# TDC.net
KiCad netlist of a schematic drawn in Altium Designer
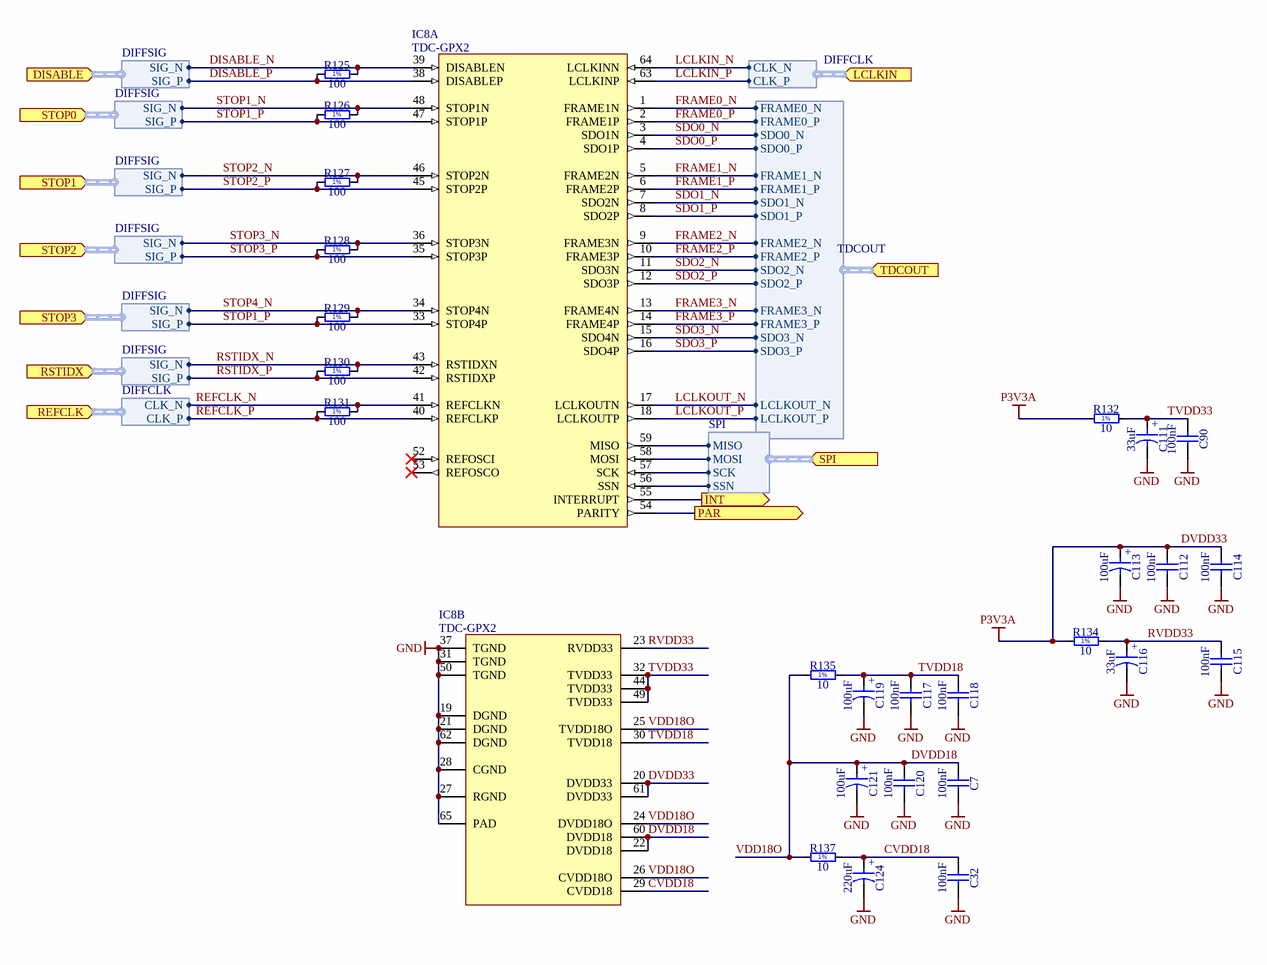
[diagram p0: TDC.SchDoc]

(export (version "E")
  (design (tool "Eeschema 10.0.6"))
  (components
    (comp (ref "C7")
      (value "100nF")
      (footprint "CAPC0603X33N")
      (description "Non-polarised capacitor")
      (fields
        (field (name "PART NUMBER") "CC0201_100NF_6.3V_10%_X5R")
        (field (name "VOLTAGE") "6.3V")
        (field (name "AUTHOR") "CERN DEM JLC")
      )
      (libsource (lib "Capacitors") (part "Capacitor - non polarized"))
    )
    (comp (ref "C32")
      (value "100nF")
      (footprint "CAPC0603X33N")
      (description "Non-polarised capacitor")
      (fields
        (field (name "PART NUMBER") "CC0201_100NF_6.3V_10%_X5R")
        (field (name "VOLTAGE") "6.3V")
        (field (name "AUTHOR") "CERN DEM JLC")
      )
      (libsource (lib "Capacitors") (part "Capacitor - non polarized"))
    )
    (comp (ref "C90")
      (value "100nF")
      (footprint "CAPC0603X33N")
      (description "Non-polarised capacitor")
      (fields
        (field (name "PART NUMBER") "CC0201_100NF_6.3V_10%_X5R")
        (field (name "VOLTAGE") "6.3V")
        (field (name "AUTHOR") "CERN DEM JLC")
      )
      (libsource (lib "Capacitors") (part "Capacitor - non polarized"))
    )
    (comp (ref "C111")
      (value "33uF")
      (footprint "CAPMP3216X180N")
      (description "Polarised capacitor")
      (fields
        (field (name "PART NUMBER") "CTE3216-18_33UF_4V_10%")
        (field (name "VOLTAGE") "4V")
        (field (name "AUTHOR") "CERN DEM JLC")
      )
      (libsource (lib "Capacitors") (part "Capacitor - polarized"))
    )
    (comp (ref "C112")
      (value "100nF")
      (footprint "CAPC0603X33N")
      (description "Non-polarised capacitor")
      (fields
        (field (name "PART NUMBER") "CC0201_100NF_6.3V_10%_X5R")
        (field (name "VOLTAGE") "6.3V")
        (field (name "AUTHOR") "CERN DEM JLC")
      )
      (libsource (lib "Capacitors") (part "Capacitor - non polarized"))
    )
    (comp (ref "C113")
      (value "100uF")
      (footprint "CAPMP3216X180N")
      (description "Polarised capacitor")
      (fields
        (field (name "PART NUMBER") "CTE3216-18_100UF_6.3V_20%_ESR0500_AVX_TLJ")
        (field (name "VOLTAGE") "6.3V")
        (field (name "AUTHOR") "CERN DEM JLC")
      )
      (libsource (lib "Capacitors") (part "Capacitor - polarized"))
    )
    (comp (ref "C114")
      (value "100nF")
      (footprint "CAPC0603X33N")
      (description "Non-polarised capacitor")
      (fields
        (field (name "PART NUMBER") "CC0201_100NF_6.3V_10%_X5R")
        (field (name "VOLTAGE") "6.3V")
        (field (name "AUTHOR") "CERN DEM JLC")
      )
      (libsource (lib "Capacitors") (part "Capacitor - non polarized"))
    )
    (comp (ref "C115")
      (value "100nF")
      (footprint "CAPC0603X33N")
      (description "Non-polarised capacitor")
      (fields
        (field (name "PART NUMBER") "CC0201_100NF_6.3V_10%_X5R")
        (field (name "VOLTAGE") "6.3V")
        (field (name "AUTHOR") "CERN DEM JLC")
      )
      (libsource (lib "Capacitors") (part "Capacitor - non polarized"))
    )
    (comp (ref "C116")
      (value "33uF")
      (footprint "CAPMP3216X180N")
      (description "Polarised capacitor")
      (fields
        (field (name "PART NUMBER") "CTE3216-18_33UF_4V_10%")
        (field (name "VOLTAGE") "4V")
        (field (name "AUTHOR") "CERN DEM JLC")
      )
      (libsource (lib "Capacitors") (part "Capacitor - polarized"))
    )
    (comp (ref "C117")
      (value "100nF")
      (footprint "CAPC0603X33N")
      (description "Non-polarised capacitor")
      (fields
        (field (name "PART NUMBER") "CC0201_100NF_6.3V_10%_X5R")
        (field (name "VOLTAGE") "6.3V")
        (field (name "AUTHOR") "CERN DEM JLC")
      )
      (libsource (lib "Capacitors") (part "Capacitor - non polarized"))
    )
    (comp (ref "C118")
      (value "100nF")
      (footprint "CAPC0603X33N")
      (description "Non-polarised capacitor")
      (fields
        (field (name "PART NUMBER") "CC0201_100NF_6.3V_10%_X5R")
        (field (name "VOLTAGE") "6.3V")
        (field (name "AUTHOR") "CERN DEM JLC")
      )
      (libsource (lib "Capacitors") (part "Capacitor - non polarized"))
    )
    (comp (ref "C119")
      (value "100uF")
      (footprint "CAPMP3216X180N")
      (description "Polarised capacitor")
      (fields
        (field (name "PART NUMBER") "CTE3216-18_100UF_6.3V_20%_ESR0500_AVX_TLJ")
        (field (name "VOLTAGE") "6.3V")
        (field (name "AUTHOR") "CERN DEM JLC")
      )
      (libsource (lib "Capacitors") (part "Capacitor - polarized"))
    )
    (comp (ref "C120")
      (value "100nF")
      (footprint "CAPC0603X33N")
      (description "Non-polarised capacitor")
      (fields
        (field (name "PART NUMBER") "CC0201_100NF_6.3V_10%_X5R")
        (field (name "VOLTAGE") "6.3V")
        (field (name "AUTHOR") "CERN DEM JLC")
      )
      (libsource (lib "Capacitors") (part "Capacitor - non polarized"))
    )
    (comp (ref "C121")
      (value "100uF")
      (footprint "CAPMP3216X180N")
      (description "Polarised capacitor")
      (fields
        (field (name "PART NUMBER") "CTE3216-18_100UF_6.3V_20%_ESR0500_AVX_TLJ")
        (field (name "VOLTAGE") "6.3V")
        (field (name "AUTHOR") "CERN DEM JLC")
      )
      (libsource (lib "Capacitors") (part "Capacitor - polarized"))
    )
    (comp (ref "C124")
      (value "220uF")
      (footprint "CAPMP3528X210N")
      (description "Polarised capacitor")
      (fields
        (field (name "PART NUMBER") "CTE3528-21_220UF_2.5V_10%")
        (field (name "VOLTAGE") "2.5V")
        (field (name "AUTHOR") "CERN DEM JLC")
      )
      (libsource (lib "Capacitors") (part "Capacitor - polarized"))
    )
    (comp (ref "IC8")
      (value "TDC-GPX2")
      (footprint "QFN50P900X900X100-65N-S615")
      (description "4-Channel Time-to-Digital Converter")
      (fields (field (name "MANUFACTURER") "ACAM MESS-ELECTRONIC") (field (name "AUTHOR") "GK"))
      (libsource (lib "LIBRARY_SCH") (part "TDC-GPX2"))
    )
    (comp (ref "R125")
      (value "100")
      (footprint "RESC0603X28N")
      (description "Resistor - 1%")
      (fields
        (field (name "PART NUMBER") "R0201_100R_1%_0.05W_200PPM")
        (field (name "POWER") "0.05W")
        (field (name "AUTHOR") "CERN DEM JLC")
      )
      (libsource (lib "Resistors") (part "Resistor - 1%"))
    )
    (comp (ref "R126")
      (value "100")
      (footprint "RESC0603X28N")
      (description "Resistor - 1%")
      (fields
        (field (name "PART NUMBER") "R0201_100R_1%_0.05W_200PPM")
        (field (name "POWER") "0.05W")
        (field (name "AUTHOR") "CERN DEM JLC")
      )
      (libsource (lib "Resistors") (part "Resistor - 1%"))
    )
    (comp (ref "R127")
      (value "100")
      (footprint "RESC0603X28N")
      (description "Resistor - 1%")
      (fields
        (field (name "PART NUMBER") "R0201_100R_1%_0.05W_200PPM")
        (field (name "POWER") "0.05W")
        (field (name "AUTHOR") "CERN DEM JLC")
      )
      (libsource (lib "Resistors") (part "Resistor - 1%"))
    )
    (comp (ref "R128")
      (value "100")
      (footprint "RESC0603X28N")
      (description "Resistor - 1%")
      (fields
        (field (name "PART NUMBER") "R0201_100R_1%_0.05W_200PPM")
        (field (name "POWER") "0.05W")
        (field (name "AUTHOR") "CERN DEM JLC")
      )
      (libsource (lib "Resistors") (part "Resistor - 1%"))
    )
    (comp (ref "R129")
      (value "100")
      (footprint "RESC0603X28N")
      (description "Resistor - 1%")
      (fields
        (field (name "PART NUMBER") "R0201_100R_1%_0.05W_200PPM")
        (field (name "POWER") "0.05W")
        (field (name "AUTHOR") "CERN DEM JLC")
      )
      (libsource (lib "Resistors") (part "Resistor - 1%"))
    )
    (comp (ref "R130")
      (value "100")
      (footprint "RESC0603X28N")
      (description "Resistor - 1%")
      (fields
        (field (name "PART NUMBER") "R0201_100R_1%_0.05W_200PPM")
        (field (name "POWER") "0.05W")
        (field (name "AUTHOR") "CERN DEM JLC")
      )
      (libsource (lib "Resistors") (part "Resistor - 1%"))
    )
    (comp (ref "R131")
      (value "100")
      (footprint "RESC0603X28N")
      (description "Resistor - 1%")
      (fields
        (field (name "PART NUMBER") "R0201_100R_1%_0.05W_200PPM")
        (field (name "POWER") "0.05W")
        (field (name "AUTHOR") "CERN DEM JLC")
      )
      (libsource (lib "Resistors") (part "Resistor - 1%"))
    )
    (comp (ref "R132")
      (value "10")
      (footprint "RESC1005X40N")
      (description "Resistor - 1%")
      (fields
        (field (name "PART NUMBER") "R0402_10R_1%_0.0625W_200PPM")
        (field (name "POWER") "0.0625W")
        (field (name "AUTHOR") "CERN DEM JLC")
      )
      (libsource (lib "Resistors") (part "Resistor - 1%"))
    )
    (comp (ref "R134")
      (value "10")
      (footprint "RESC1005X40N")
      (description "Resistor - 1%")
      (fields
        (field (name "PART NUMBER") "R0402_10R_1%_0.0625W_200PPM")
        (field (name "POWER") "0.0625W")
        (field (name "AUTHOR") "CERN DEM JLC")
      )
      (libsource (lib "Resistors") (part "Resistor - 1%"))
    )
    (comp (ref "R135")
      (value "10")
      (footprint "RESC1005X40N")
      (description "Resistor - 1%")
      (fields
        (field (name "PART NUMBER") "R0402_10R_1%_0.0625W_200PPM")
        (field (name "POWER") "0.0625W")
        (field (name "AUTHOR") "CERN DEM JLC")
      )
      (libsource (lib "Resistors") (part "Resistor - 1%"))
    )
    (comp (ref "R137")
      (value "10")
      (footprint "RESC1005X40N")
      (description "Resistor - 1%")
      (fields
        (field (name "PART NUMBER") "R0402_10R_1%_0.0625W_200PPM")
        (field (name "POWER") "0.0625W")
        (field (name "AUTHOR") "CERN DEM JLC")
      )
      (libsource (lib "Resistors") (part "Resistor - 1%"))
    )
  )
  (nets
    (net (code "5") (name "/CVDD18") (class "Default")
      (node (ref "C124") (pin "1") (pinfunction "1_1") (pintype "passive"))
      (node (ref "C32") (pin "1") (pinfunction "1_1") (pintype "passive"))
      (node (ref "IC8") (pin "29") (pinfunction "CVDD18_29") (pintype "power_in"))
      (node (ref "R137") (pin "2") (pinfunction "2_2") (pintype "passive"))
    )
    (net (code "6") (name "/DISABLE_N") (class "Default")
      (node (ref "IC8") (pin "39") (pinfunction "DISABLEN_39") (pintype "input"))
      (node (ref "R125") (pin "2") (pinfunction "2_2") (pintype "passive"))
    )
    (net (code "7") (name "/DISABLE_P") (class "Default")
      (node (ref "IC8") (pin "38") (pinfunction "DISABLEP_38") (pintype "input"))
      (node (ref "R125") (pin "1") (pinfunction "1_1") (pintype "passive"))
    )
    (net (code "8") (name "/DVDD18") (class "Default")
      (node (ref "C120") (pin "1") (pinfunction "1_1") (pintype "passive"))
      (node (ref "C121") (pin "1") (pinfunction "1_1") (pintype "passive"))
      (node (ref "C7") (pin "1") (pinfunction "1_1") (pintype "passive"))
      (node (ref "IC8") (pin "22") (pinfunction "DVDD18_22") (pintype "power_in"))
      (node (ref "IC8") (pin "24") (pinfunction "DVDD18O_24") (pintype "power_in"))
      (node (ref "IC8") (pin "25") (pinfunction "TVDD18O_25") (pintype "power_in"))
      (node (ref "IC8") (pin "26") (pinfunction "CVDD18O_26") (pintype "power_in"))
      (node (ref "IC8") (pin "60") (pinfunction "DVDD18_60") (pintype "power_in"))
      (node (ref "R135") (pin "1") (pinfunction "1_1") (pintype "passive"))
      (node (ref "R137") (pin "1") (pinfunction "1_1") (pintype "passive"))
    )
    (net (code "9") (name "/FRAME0_N") (class "Default")
      (node (ref "IC8") (pin "1") (pinfunction "FRAME1N_1") (pintype "output"))
    )
    (net (code "10") (name "/FRAME0_P") (class "Default")
      (node (ref "IC8") (pin "2") (pinfunction "FRAME1P_2") (pintype "output"))
    )
    (net (code "11") (name "/FRAME1_N") (class "Default")
      (node (ref "IC8") (pin "5") (pinfunction "FRAME2N_5") (pintype "output"))
    )
    (net (code "12") (name "/FRAME1_P") (class "Default")
      (node (ref "IC8") (pin "6") (pinfunction "FRAME2P_6") (pintype "output"))
    )
    (net (code "13") (name "/FRAME2_N") (class "Default")
      (node (ref "IC8") (pin "9") (pinfunction "FRAME3N_9") (pintype "output"))
    )
    (net (code "14") (name "/FRAME2_P") (class "Default")
      (node (ref "IC8") (pin "10") (pinfunction "FRAME3P_10") (pintype "output"))
    )
    (net (code "15") (name "/FRAME3_N") (class "Default")
      (node (ref "IC8") (pin "13") (pinfunction "FRAME4N_13") (pintype "output"))
    )
    (net (code "16") (name "/FRAME3_P") (class "Default")
      (node (ref "IC8") (pin "14") (pinfunction "FRAME4P_14") (pintype "output"))
    )
    (net (code "17") (name "/INT") (class "Default")
      (node (ref "IC8") (pin "55") (pinfunction "INTERRUPT_55") (pintype "output"))
    )
    (net (code "18") (name "/LCLKIN_N") (class "Default")
      (node (ref "IC8") (pin "64") (pinfunction "LCLKINN_64") (pintype "input"))
    )
    (net (code "19") (name "/LCLKIN_P") (class "Default")
      (node (ref "IC8") (pin "63") (pinfunction "LCLKINP_63") (pintype "input"))
    )
    (net (code "20") (name "/LCLKOUT_N") (class "Default")
      (node (ref "IC8") (pin "17") (pinfunction "LCLKOUTN_17") (pintype "output"))
    )
    (net (code "21") (name "/LCLKOUT_P") (class "Default")
      (node (ref "IC8") (pin "18") (pinfunction "LCLKOUTP_18") (pintype "output"))
    )
    (net (code "22") (name "/MISO") (class "Default")
      (node (ref "IC8") (pin "59") (pinfunction "MISO_59") (pintype "output"))
    )
    (net (code "23") (name "/MOSI") (class "Default")
      (node (ref "IC8") (pin "58") (pinfunction "MOSI_58") (pintype "input"))
    )
    (net (code "24") (name "/PAR") (class "Default")
      (node (ref "IC8") (pin "54") (pinfunction "PARITY_54") (pintype "output"))
    )
    (net (code "25") (name "/REFCLK_N") (class "Default")
      (node (ref "IC8") (pin "41") (pinfunction "REFCLKN_41") (pintype "input"))
      (node (ref "R131") (pin "2") (pinfunction "2_2") (pintype "passive"))
    )
    (net (code "26") (name "/REFCLK_P") (class "Default")
      (node (ref "IC8") (pin "40") (pinfunction "REFCLKP_40") (pintype "input"))
      (node (ref "R131") (pin "1") (pinfunction "1_1") (pintype "passive"))
    )
    (net (code "27") (name "/RSTIDX_N") (class "Default")
      (node (ref "IC8") (pin "43") (pinfunction "RSTIDXN_43") (pintype "input"))
      (node (ref "R130") (pin "2") (pinfunction "2_2") (pintype "passive"))
    )
    (net (code "28") (name "/RSTIDX_P") (class "Default")
      (node (ref "IC8") (pin "42") (pinfunction "RSTIDXP_42") (pintype "input"))
      (node (ref "R130") (pin "1") (pinfunction "1_1") (pintype "passive"))
    )
    (net (code "29") (name "/RVDD33") (class "Default")
      (node (ref "C115") (pin "1") (pinfunction "1_1") (pintype "passive"))
      (node (ref "C116") (pin "1") (pinfunction "1_1") (pintype "passive"))
      (node (ref "IC8") (pin "23") (pinfunction "RVDD33_23") (pintype "power_in"))
      (node (ref "R134") (pin "2") (pinfunction "2_2") (pintype "passive"))
    )
    (net (code "30") (name "/SCK") (class "Default")
      (node (ref "IC8") (pin "57") (pinfunction "SCK_57") (pintype "input"))
    )
    (net (code "31") (name "/SDO0_N") (class "Default")
      (node (ref "IC8") (pin "3") (pinfunction "SDO1N_3") (pintype "output"))
    )
    (net (code "32") (name "/SDO0_P") (class "Default")
      (node (ref "IC8") (pin "4") (pinfunction "SDO1P_4") (pintype "output"))
    )
    (net (code "33") (name "/SDO1_N") (class "Default")
      (node (ref "IC8") (pin "7") (pinfunction "SDO2N_7") (pintype "output"))
    )
    (net (code "34") (name "/SDO1_P") (class "Default")
      (node (ref "IC8") (pin "8") (pinfunction "SDO2P_8") (pintype "output"))
    )
    (net (code "35") (name "/SDO2_N") (class "Default")
      (node (ref "IC8") (pin "11") (pinfunction "SDO3N_11") (pintype "output"))
    )
    (net (code "36") (name "/SDO2_P") (class "Default")
      (node (ref "IC8") (pin "12") (pinfunction "SDO3P_12") (pintype "output"))
    )
    (net (code "37") (name "/SDO3_N") (class "Default")
      (node (ref "IC8") (pin "15") (pinfunction "SDO4N_15") (pintype "output"))
    )
    (net (code "38") (name "/SDO3_P") (class "Default")
      (node (ref "IC8") (pin "16") (pinfunction "SDO4P_16") (pintype "output"))
    )
    (net (code "39") (name "/SSN") (class "Default")
      (node (ref "IC8") (pin "56") (pinfunction "SSN_56") (pintype "input"))
    )
    (net (code "40") (name "/STOP1_N") (class "Default")
      (node (ref "IC8") (pin "48") (pinfunction "STOP1N_48") (pintype "input"))
      (node (ref "R126") (pin "2") (pinfunction "2_2") (pintype "passive"))
    )
    (net (code "41") (name "/STOP1_P") (class "Default")
      (node (ref "IC8") (pin "33") (pinfunction "STOP4P_33") (pintype "input"))
      (node (ref "IC8") (pin "47") (pinfunction "STOP1P_47") (pintype "input"))
      (node (ref "R126") (pin "1") (pinfunction "1_1") (pintype "passive"))
      (node (ref "R129") (pin "1") (pinfunction "1_1") (pintype "passive"))
    )
    (net (code "42") (name "/STOP2_N") (class "Default")
      (node (ref "IC8") (pin "46") (pinfunction "STOP2N_46") (pintype "input"))
      (node (ref "R127") (pin "2") (pinfunction "2_2") (pintype "passive"))
    )
    (net (code "43") (name "/STOP2_P") (class "Default")
      (node (ref "IC8") (pin "45") (pinfunction "STOP2P_45") (pintype "input"))
      (node (ref "R127") (pin "1") (pinfunction "1_1") (pintype "passive"))
    )
    (net (code "44") (name "/STOP3_N") (class "Default")
      (node (ref "IC8") (pin "36") (pinfunction "STOP3N_36") (pintype "input"))
      (node (ref "R128") (pin "2") (pinfunction "2_2") (pintype "passive"))
    )
    (net (code "45") (name "/STOP3_P") (class "Default")
      (node (ref "IC8") (pin "35") (pinfunction "STOP3P_35") (pintype "input"))
      (node (ref "R128") (pin "1") (pinfunction "1_1") (pintype "passive"))
    )
    (net (code "46") (name "/STOP4_N") (class "Default")
      (node (ref "IC8") (pin "34") (pinfunction "STOP4N_34") (pintype "input"))
      (node (ref "R129") (pin "2") (pinfunction "2_2") (pintype "passive"))
    )
    (net (code "47") (name "/TVDD18") (class "Default")
      (node (ref "C117") (pin "1") (pinfunction "1_1") (pintype "passive"))
      (node (ref "C118") (pin "1") (pinfunction "1_1") (pintype "passive"))
      (node (ref "C119") (pin "1") (pinfunction "1_1") (pintype "passive"))
      (node (ref "IC8") (pin "30") (pinfunction "TVDD18_30") (pintype "power_in"))
      (node (ref "R135") (pin "2") (pinfunction "2_2") (pintype "passive"))
    )
    (net (code "48") (name "/TVDD33") (class "Default")
      (node (ref "C111") (pin "1") (pinfunction "1_1") (pintype "passive"))
      (node (ref "C90") (pin "1") (pinfunction "1_1") (pintype "passive"))
      (node (ref "IC8") (pin "32") (pinfunction "TVDD33_32") (pintype "power_in"))
      (node (ref "IC8") (pin "44") (pinfunction "TVDD33_44") (pintype "power_in"))
      (node (ref "IC8") (pin "49") (pinfunction "TVDD33_49") (pintype "power_in"))
      (node (ref "R132") (pin "2") (pinfunction "2_2") (pintype "passive"))
    )
    (net (code "53") (name "GND") (class "Default")
      (node (ref "C111") (pin "2") (pinfunction "2_2") (pintype "passive"))
      (node (ref "C112") (pin "2") (pinfunction "2_2") (pintype "passive"))
      (node (ref "C113") (pin "2") (pinfunction "2_2") (pintype "passive"))
      (node (ref "C114") (pin "2") (pinfunction "2_2") (pintype "passive"))
      (node (ref "C115") (pin "2") (pinfunction "2_2") (pintype "passive"))
      (node (ref "C116") (pin "2") (pinfunction "2_2") (pintype "passive"))
      (node (ref "C117") (pin "2") (pinfunction "2_2") (pintype "passive"))
      (node (ref "C118") (pin "2") (pinfunction "2_2") (pintype "passive"))
      (node (ref "C119") (pin "2") (pinfunction "2_2") (pintype "passive"))
      (node (ref "C120") (pin "2") (pinfunction "2_2") (pintype "passive"))
      (node (ref "C121") (pin "2") (pinfunction "2_2") (pintype "passive"))
      (node (ref "C124") (pin "2") (pinfunction "2_2") (pintype "passive"))
      (node (ref "C32") (pin "2") (pinfunction "2_2") (pintype "passive"))
      (node (ref "C7") (pin "2") (pinfunction "2_2") (pintype "passive"))
      (node (ref "C90") (pin "2") (pinfunction "2_2") (pintype "passive"))
      (node (ref "IC8") (pin "19") (pinfunction "DGND_19") (pintype "power_in"))
      (node (ref "IC8") (pin "21") (pinfunction "DGND_21") (pintype "power_in"))
      (node (ref "IC8") (pin "27") (pinfunction "RGND_27") (pintype "power_in"))
      (node (ref "IC8") (pin "28") (pinfunction "CGND_28") (pintype "power_in"))
      (node (ref "IC8") (pin "31") (pinfunction "TGND_31") (pintype "power_in"))
      (node (ref "IC8") (pin "37") (pinfunction "TGND_37") (pintype "power_in"))
      (node (ref "IC8") (pin "50") (pinfunction "TGND_50") (pintype "power_in"))
      (node (ref "IC8") (pin "62") (pinfunction "DGND_62") (pintype "power_in"))
      (node (ref "IC8") (pin "65") (pinfunction "PAD_65") (pintype "power_in"))
    )
    (net (code "54") (name "P3V3A") (class "Default")
      (node (ref "C112") (pin "1") (pinfunction "1_1") (pintype "passive"))
      (node (ref "C113") (pin "1") (pinfunction "1_1") (pintype "passive"))
      (node (ref "C114") (pin "1") (pinfunction "1_1") (pintype "passive"))
      (node (ref "IC8") (pin "20") (pinfunction "DVDD33_20") (pintype "power_in"))
      (node (ref "IC8") (pin "61") (pinfunction "DVDD33_61") (pintype "power_in"))
      (node (ref "R132") (pin "1") (pinfunction "1_1") (pintype "passive"))
      (node (ref "R134") (pin "1") (pinfunction "1_1") (pintype "passive"))
    )
    (net (code "55") (name "unconnected-(IC8A-REFOSCI-Pad52)") (class "Default")
      (node (ref "IC8") (pin "52") (pinfunction "REFOSCI_52") (pintype "input+no_connect"))
    )
    (net (code "56") (name "unconnected-(IC8A-REFOSCO-Pad53)") (class "Default")
      (node (ref "IC8") (pin "53") (pinfunction "REFOSCO_53") (pintype "output+no_connect"))
    )
  )
)
